# Minidev_V1_0.net
KiCad netlist of a schematic drawn in EAGLE
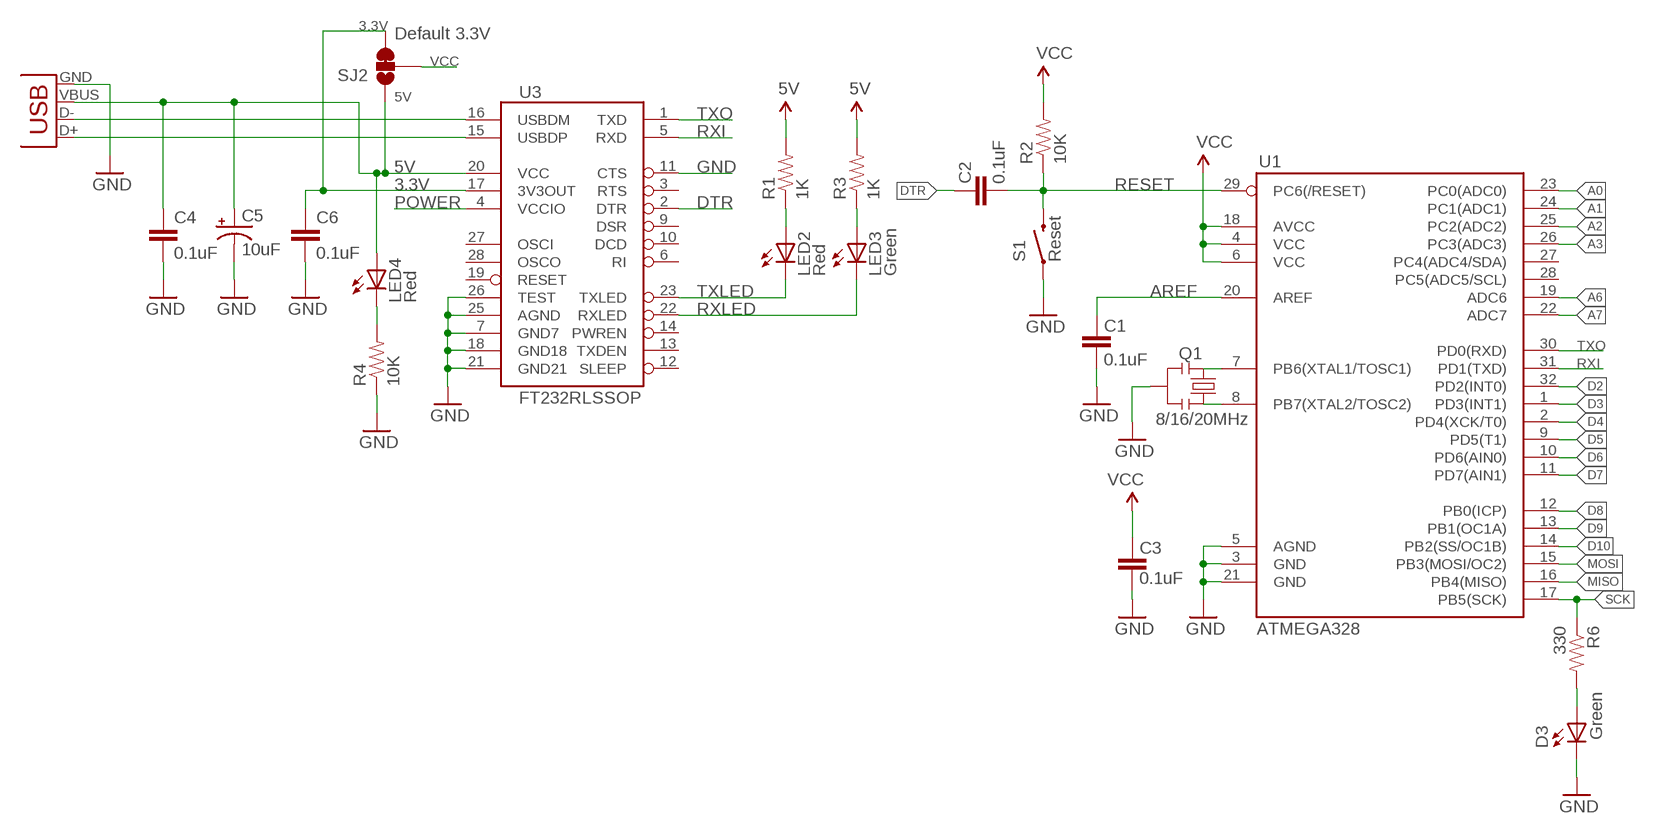
[diagram p0: schematic, sheet 1]

(export (version "E")
  (design (tool "Eeschema 10.0.6"))
  (components
    (comp (ref "C1")
      (value "0.1uF")
      (footprint "eagle-import:0603-CAP")
      (libsource (lib "eagle-import") (part "CAP0603-CAP"))
    )
    (comp (ref "C2")
      (value "0.1uF")
      (footprint "eagle-import:0603-CAP")
      (libsource (lib "eagle-import") (part "CAP0603-CAP"))
    )
    (comp (ref "C3")
      (value "0.1uF")
      (footprint "eagle-import:0603-CAP")
      (libsource (lib "eagle-import") (part "CAP0603-CAP"))
    )
    (comp (ref "C4")
      (value "0.1uF")
      (footprint "eagle-import:0402-CAP")
      (libsource (lib "eagle-import") (part "CAP0402-CAP"))
    )
    (comp (ref "C5")
      (value "10uF")
      (footprint "eagle-import:EIA3216")
      (libsource (lib "eagle-import") (part "CAP_POL1206"))
    )
    (comp (ref "C6")
      (value "0.1uF")
      (footprint "eagle-import:0402-CAP")
      (libsource (lib "eagle-import") (part "CAP0402-CAP"))
    )
    (comp (ref "D3")
      (value "Green")
      (footprint "eagle-import:0603-LED-ALT1")
      (libsource (lib "eagle-import") (part "LED"))
    )
    (comp (ref "LED2")
      (value "Red")
      (footprint "eagle-import:LED-0603")
      (libsource (lib "eagle-import") (part "LED0603"))
    )
    (comp (ref "LED3")
      (value "Green")
      (footprint "eagle-import:LED-0603")
      (libsource (lib "eagle-import") (part "LED0603"))
    )
    (comp (ref "LED4")
      (value "Red")
      (footprint "eagle-import:0603-LED-ALT1")
      (libsource (lib "eagle-import") (part "LED"))
    )
    (comp (ref "Q1")
      (value "8/16/20MHz")
      (footprint "eagle-import:RESONATOR-SMD-1_1")
      (libsource (lib "eagle-import") (part "RESONATOR1{colon}1"))
    )
    (comp (ref "R1")
      (value "1K")
      (footprint "eagle-import:0402-RES")
      (libsource (lib "eagle-import") (part "RESISTOR0402-RES"))
    )
    (comp (ref "R2")
      (value "10K")
      (footprint "eagle-import:0603-RES")
      (libsource (lib "eagle-import") (part "RESISTOR0603-RES"))
    )
    (comp (ref "R3")
      (value "1K")
      (footprint "eagle-import:0402-RES")
      (libsource (lib "eagle-import") (part "RESISTOR0402-RES"))
    )
    (comp (ref "R4")
      (value "10K")
      (footprint "eagle-import:0603-RES")
      (libsource (lib "eagle-import") (part "RESISTOR0603-RES"))
    )
    (comp (ref "R6")
      (value "330")
      (footprint "eagle-import:0603-RES")
      (libsource (lib "eagle-import") (part "RESISTOR0603-RES"))
    )
    (comp (ref "S1")
      (value "Reset")
      (footprint "eagle-import:TACTILE-SWITCH-SMD-ALT01")
      (libsource (lib "eagle-import") (part "SWITCH-MOMENTARY-2SMD-ALT01"))
    )
    (comp (ref "SJ2")
      (value "SOLDERJUMPER_2WAYS")
      (footprint "eagle-import:SJ_3")
      (libsource (lib "eagle-import") (part "SOLDERJUMPER_2WAYS"))
    )
    (comp (ref "U1")
      (value "ATMEGA328")
      (footprint "eagle-import:TQFP32-08")
      (libsource (lib "eagle-import") (part "ATMEGA168"))
    )
    (comp (ref "U3")
      (value "FT232RLSSOP")
      (footprint "eagle-import:SSOP28DB")
      (libsource (lib "eagle-import") (part "FT232RLSSOP"))
    )
    (comp (ref "X2")
      (value "USB-SMD-NS")
      (footprint "eagle-import:USB-MINIB-NOSTOP")
      (libsource (lib "eagle-import") (part "USB-SMD-NS"))
    )
  )
  (nets
    (net (code "1") (name "/3.3V") (class "Default")
      (node (ref "C6") (pin "1") (pinfunction "1_1") (pintype "passive"))
      (node (ref "SJ2") (pin "3") (pinfunction "3_3") (pintype "passive"))
      (node (ref "U3") (pin "17") (pinfunction "3V3OUT_17") (pintype "output"))
    )
    (net (code "2") (name "/AREF") (class "Default")
      (node (ref "C1") (pin "2") (pinfunction "2_2") (pintype "passive"))
      (node (ref "U1") (pin "20") (pinfunction "AREF_20") (pintype "bidirectional"))
    )
    (net (code "3") (name "/POWER") (class "Default")
      (node (ref "U3") (pin "4") (pinfunction "VCCIO_4") (pintype "power_in"))
    )
    (net (code "4") (name "/RESET") (class "Default")
      (node (ref "C2") (pin "1") (pinfunction "1_1") (pintype "passive"))
      (node (ref "R2") (pin "1") (pinfunction "1_1") (pintype "passive"))
      (node (ref "S1") (pin "3") (pinfunction "2_3") (pintype "passive"))
      (node (ref "S1") (pin "4") (pinfunction "2_4") (pintype "passive"))
      (node (ref "U1") (pin "29") (pinfunction "PC6(/RESET)_29") (pintype "bidirectional"))
    )
    (net (code "5") (name "/RXI") (class "Default")
      (node (ref "U1") (pin "31") (pinfunction "PD1(TXD)_31") (pintype "bidirectional"))
      (node (ref "U3") (pin "5") (pinfunction "RXD_5") (pintype "input"))
    )
    (net (code "6") (name "/RXLED") (class "Default")
      (node (ref "LED3") (pin "C") (pinfunction "C_C") (pintype "passive"))
      (node (ref "U3") (pin "22") (pinfunction "RXLED_22") (pintype "input"))
    )
    (net (code "7") (name "/TXLED") (class "Default")
      (node (ref "LED2") (pin "C") (pinfunction "C_C") (pintype "passive"))
      (node (ref "U3") (pin "23") (pinfunction "TXLED_23") (pintype "input"))
    )
    (net (code "8") (name "/TXO") (class "Default")
      (node (ref "U1") (pin "30") (pinfunction "PD0(RXD)_30") (pintype "bidirectional"))
      (node (ref "U3") (pin "1") (pinfunction "TXD_1") (pintype "output"))
    )
    (net (code "9") (name "5V") (class "Default")
      (node (ref "C4") (pin "1") (pinfunction "1_1") (pintype "passive"))
      (node (ref "C5") (pin "A") (pinfunction "+_A") (pintype "passive"))
      (node (ref "LED4") (pin "A") (pinfunction "A_A") (pintype "passive"))
      (node (ref "R1") (pin "2") (pinfunction "2_2") (pintype "passive"))
      (node (ref "R3") (pin "2") (pinfunction "2_2") (pintype "passive"))
      (node (ref "SJ2") (pin "1") (pinfunction "1_1") (pintype "passive"))
      (node (ref "U3") (pin "20") (pinfunction "VCC_20") (pintype "power_in"))
      (node (ref "X2") (pin "VBUS") (pinfunction "VBUS_VBUS") (pintype "bidirectional"))
    )
    (net (code "10") (name "A0") (class "Default")
      (node (ref "U1") (pin "23") (pinfunction "PC0(ADC0)_23") (pintype "bidirectional"))
    )
    (net (code "11") (name "A1") (class "Default")
      (node (ref "U1") (pin "24") (pinfunction "PC1(ADC1)_24") (pintype "bidirectional"))
    )
    (net (code "12") (name "A2") (class "Default")
      (node (ref "U1") (pin "25") (pinfunction "PC2(ADC2)_25") (pintype "bidirectional"))
    )
    (net (code "13") (name "A3") (class "Default")
      (node (ref "U1") (pin "26") (pinfunction "PC3(ADC3)_26") (pintype "bidirectional"))
    )
    (net (code "14") (name "A6") (class "Default")
      (node (ref "U1") (pin "19") (pinfunction "ADC6_19") (pintype "bidirectional"))
    )
    (net (code "15") (name "A7") (class "Default")
      (node (ref "U1") (pin "22") (pinfunction "ADC7_22") (pintype "bidirectional"))
    )
    (net (code "16") (name "D2") (class "Default")
      (node (ref "U1") (pin "32") (pinfunction "PD2(INT0)_32") (pintype "bidirectional"))
    )
    (net (code "17") (name "D3") (class "Default")
      (node (ref "U1") (pin "1") (pinfunction "PD3(INT1)_1") (pintype "bidirectional"))
    )
    (net (code "18") (name "D4") (class "Default")
      (node (ref "U1") (pin "2") (pinfunction "PD4(XCK/T0)_2") (pintype "bidirectional"))
    )
    (net (code "19") (name "D5") (class "Default")
      (node (ref "U1") (pin "9") (pinfunction "PD5(T1)_9") (pintype "bidirectional"))
    )
    (net (code "20") (name "D6") (class "Default")
      (node (ref "U1") (pin "10") (pinfunction "PD6(AIN0)_10") (pintype "bidirectional"))
    )
    (net (code "21") (name "D7") (class "Default")
      (node (ref "U1") (pin "11") (pinfunction "PD7(AIN1)_11") (pintype "bidirectional"))
    )
    (net (code "22") (name "D8") (class "Default")
      (node (ref "U1") (pin "12") (pinfunction "PB0(ICP)_12") (pintype "bidirectional"))
    )
    (net (code "23") (name "D9") (class "Default")
      (node (ref "U1") (pin "13") (pinfunction "PB1(OC1A)_13") (pintype "bidirectional"))
    )
    (net (code "24") (name "D10") (class "Default")
      (node (ref "U1") (pin "14") (pinfunction "PB2(SS/OC1B)_14") (pintype "bidirectional"))
    )
    (net (code "25") (name "DTR") (class "Default")
      (node (ref "C2") (pin "2") (pinfunction "2_2") (pintype "passive"))
      (node (ref "U3") (pin "2") (pinfunction "DTR_2") (pintype "output"))
    )
    (net (code "26") (name "GND") (class "Default")
      (node (ref "C1") (pin "1") (pinfunction "1_1") (pintype "passive"))
      (node (ref "C3") (pin "1") (pinfunction "1_1") (pintype "passive"))
      (node (ref "C4") (pin "2") (pinfunction "2_2") (pintype "passive"))
      (node (ref "C5") (pin "C") (pinfunction "-_C") (pintype "passive"))
      (node (ref "C6") (pin "2") (pinfunction "2_2") (pintype "passive"))
      (node (ref "D3") (pin "C") (pinfunction "C_C") (pintype "passive"))
      (node (ref "Q1") (pin "2") (pinfunction "2_2") (pintype "passive"))
      (node (ref "R4") (pin "1") (pinfunction "1_1") (pintype "passive"))
      (node (ref "S1") (pin "1") (pinfunction "1_1") (pintype "passive"))
      (node (ref "S1") (pin "2") (pinfunction "1_2") (pintype "passive"))
      (node (ref "U1") (pin "21") (pinfunction "GND_21") (pintype "bidirectional"))
      (node (ref "U1") (pin "3") (pinfunction "GND_3") (pintype "bidirectional"))
      (node (ref "U1") (pin "5") (pinfunction "AGND_5") (pintype "bidirectional"))
      (node (ref "U3") (pin "11") (pinfunction "CTS_11") (pintype "input"))
      (node (ref "U3") (pin "18") (pinfunction "GND18_18") (pintype "power_in"))
      (node (ref "U3") (pin "21") (pinfunction "GND21_21") (pintype "power_in"))
      (node (ref "U3") (pin "25") (pinfunction "AGND_25") (pintype "power_in"))
      (node (ref "U3") (pin "26") (pinfunction "TEST_26") (pintype "input"))
      (node (ref "U3") (pin "7") (pinfunction "GND7_7") (pintype "power_in"))
      (node (ref "X2") (pin "GND") (pinfunction "GND_GND") (pintype "bidirectional"))
    )
    (net (code "27") (name "MISO") (class "Default")
      (node (ref "U1") (pin "16") (pinfunction "PB4(MISO)_16") (pintype "bidirectional"))
    )
    (net (code "28") (name "MOSI") (class "Default")
      (node (ref "U1") (pin "15") (pinfunction "PB3(MOSI/OC2)_15") (pintype "bidirectional"))
    )
    (net (code "29") (name "Net-(D3-PadA)") (class "Default")
      (node (ref "D3") (pin "A") (pinfunction "A_A") (pintype "passive"))
      (node (ref "R6") (pin "2") (pinfunction "2_2") (pintype "passive"))
    )
    (net (code "30") (name "Net-(LED2-PadA)") (class "Default")
      (node (ref "LED2") (pin "A") (pinfunction "A_A") (pintype "passive"))
      (node (ref "R1") (pin "1") (pinfunction "1_1") (pintype "passive"))
    )
    (net (code "31") (name "Net-(LED3-PadA)") (class "Default")
      (node (ref "LED3") (pin "A") (pinfunction "A_A") (pintype "passive"))
      (node (ref "R3") (pin "1") (pinfunction "1_1") (pintype "passive"))
    )
    (net (code "32") (name "Net-(LED4-PadC)") (class "Default")
      (node (ref "LED4") (pin "C") (pinfunction "C_C") (pintype "passive"))
      (node (ref "R4") (pin "2") (pinfunction "2_2") (pintype "passive"))
    )
    (net (code "33") (name "Net-(U1-PB6(XTAL1{slash}TOSC1))") (class "Default")
      (node (ref "Q1") (pin "1") (pinfunction "1_1") (pintype "passive"))
      (node (ref "U1") (pin "7") (pinfunction "PB6(XTAL1/TOSC1)_7") (pintype "bidirectional"))
    )
    (net (code "34") (name "Net-(U1-PB7(XTAL2{slash}TOSC2))") (class "Default")
      (node (ref "Q1") (pin "3") (pinfunction "3_3") (pintype "passive"))
      (node (ref "U1") (pin "8") (pinfunction "PB7(XTAL2/TOSC2)_8") (pintype "bidirectional"))
    )
    (net (code "35") (name "Net-(U3-USBDM)") (class "Default")
      (node (ref "U3") (pin "16") (pinfunction "USBDM_16") (pintype "bidirectional"))
      (node (ref "X2") (pin "D-") (pinfunction "D-_D-") (pintype "bidirectional"))
    )
    (net (code "36") (name "Net-(U3-USBDP)") (class "Default")
      (node (ref "U3") (pin "15") (pinfunction "USBDP_15") (pintype "bidirectional"))
      (node (ref "X2") (pin "D+") (pinfunction "D+_D+") (pintype "bidirectional"))
    )
    (net (code "37") (name "SCK") (class "Default")
      (node (ref "R6") (pin "1") (pinfunction "1_1") (pintype "passive"))
      (node (ref "U1") (pin "17") (pinfunction "PB5(SCK)_17") (pintype "bidirectional"))
    )
    (net (code "38") (name "VCC") (class "Default")
      (node (ref "C3") (pin "2") (pinfunction "2_2") (pintype "passive"))
      (node (ref "R2") (pin "2") (pinfunction "2_2") (pintype "passive"))
      (node (ref "SJ2") (pin "2") (pinfunction "2_2") (pintype "passive"))
      (node (ref "U1") (pin "18") (pinfunction "AVCC_18") (pintype "bidirectional"))
      (node (ref "U1") (pin "4") (pinfunction "VCC_4") (pintype "bidirectional"))
      (node (ref "U1") (pin "6") (pinfunction "VCC_6") (pintype "bidirectional"))
    )
    (net (code "39") (name "unconnected-(U1-PC4(ADC4{slash}SDA)-Pad27)") (class "Default")
      (node (ref "U1") (pin "27") (pinfunction "PC4(ADC4/SDA)_27") (pintype "bidirectional"))
    )
    (net (code "40") (name "unconnected-(U1-PC5(ADC5{slash}SCL)-Pad28)") (class "Default")
      (node (ref "U1") (pin "28") (pinfunction "PC5(ADC5/SCL)_28") (pintype "bidirectional"))
    )
    (net (code "41") (name "unconnected-(U3-DCD-Pad10)") (class "Default")
      (node (ref "U3") (pin "10") (pinfunction "DCD_10") (pintype "input"))
    )
    (net (code "42") (name "unconnected-(U3-DSR-Pad9)") (class "Default")
      (node (ref "U3") (pin "9") (pinfunction "DSR_9") (pintype "input"))
    )
    (net (code "43") (name "unconnected-(U3-OSCI-Pad27)") (class "Default")
      (node (ref "U3") (pin "27") (pinfunction "OSCI_27") (pintype "input"))
    )
    (net (code "44") (name "unconnected-(U3-OSCO-Pad28)") (class "Default")
      (node (ref "U3") (pin "28") (pinfunction "OSCO_28") (pintype "output"))
    )
    (net (code "45") (name "unconnected-(U3-PWREN-Pad14)") (class "Default")
      (node (ref "U3") (pin "14") (pinfunction "PWREN_14") (pintype "input"))
    )
    (net (code "46") (name "unconnected-(U3-RESET-Pad19)") (class "Default")
      (node (ref "U3") (pin "19") (pinfunction "RESET_19") (pintype "input"))
    )
    (net (code "47") (name "unconnected-(U3-RI-Pad6)") (class "Default")
      (node (ref "U3") (pin "6") (pinfunction "RI_6") (pintype "input"))
    )
    (net (code "48") (name "unconnected-(U3-RTS-Pad3)") (class "Default")
      (node (ref "U3") (pin "3") (pinfunction "RTS_3") (pintype "output"))
    )
    (net (code "49") (name "unconnected-(U3-SLEEP-Pad12)") (class "Default")
      (node (ref "U3") (pin "12") (pinfunction "SLEEP_12") (pintype "input"))
    )
    (net (code "50") (name "unconnected-(U3-TXDEN-Pad13)") (class "Default")
      (node (ref "U3") (pin "13") (pinfunction "TXDEN_13") (pintype "input"))
    )
  )
)
